# eeZeePot.net
KiCad netlist of a schematic drawn in EAGLE
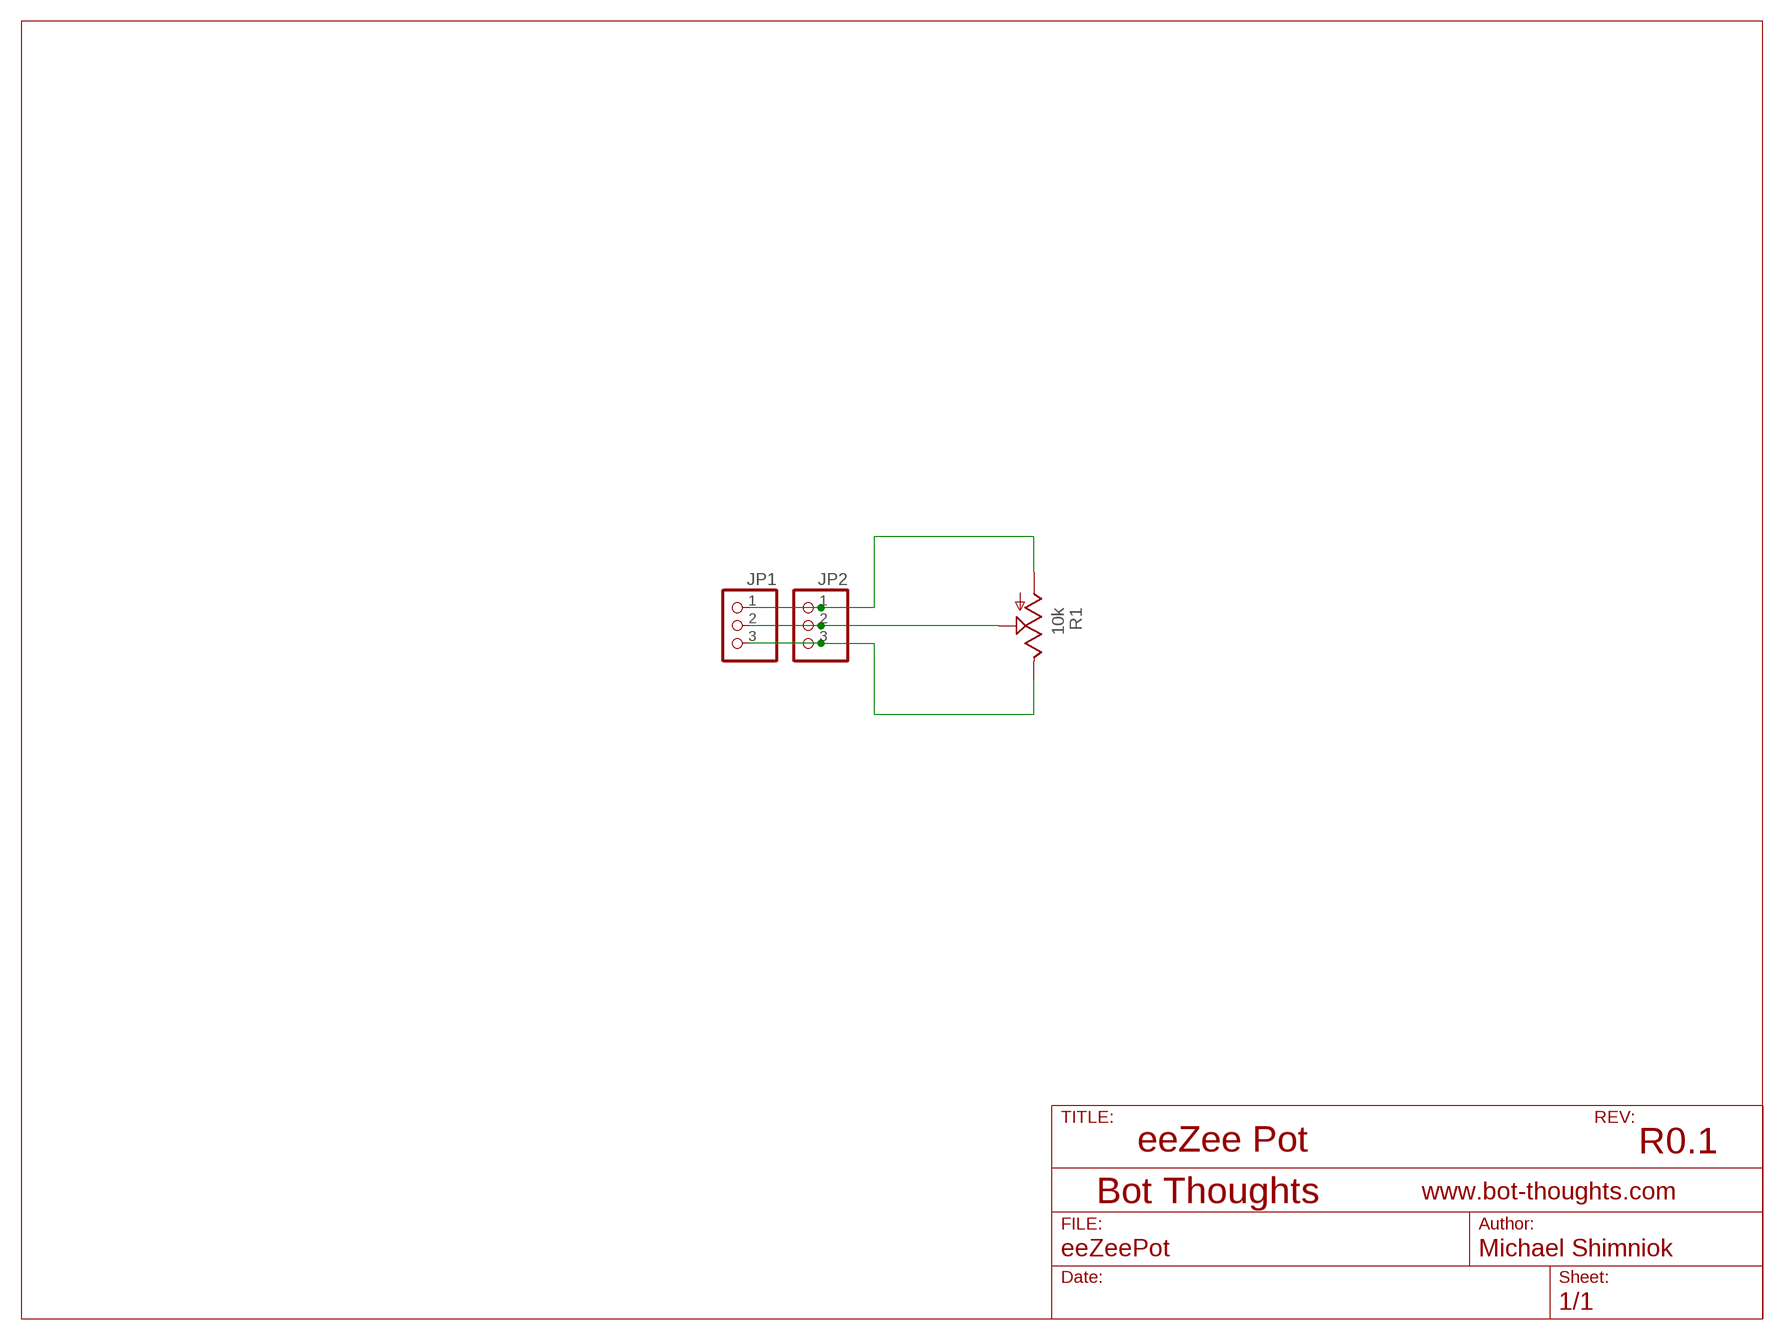
[diagram p0: schematic, sheet 1]

(export (version "E")
  (design (tool "Eeschema 10.0.6"))
  (components
    (comp (ref "JP1")
      (value "PINHD-1X03_2.54-S")
      (footprint "eagle-import:1X03-S")
      (libsource (lib "eagle-import") (part "PINHD-1X03_2.54-S"))
    )
    (comp (ref "JP2")
      (value "PINHD-1X03_2.54-S")
      (footprint "eagle-import:1X03-S")
      (libsource (lib "eagle-import") (part "PINHD-1X03_2.54-S"))
    )
    (comp (ref "R1")
      (value "10k")
      (footprint "eagle-import:CA6V")
      (libsource (lib "eagle-import") (part "TRIM_US-CA6V"))
    )
  )
  (nets
    (net (code "1") (name "Net-(JP1-Pad1)") (class "Default")
      (node (ref "JP1") (pin "1") (pinfunction "1_1") (pintype "passive"))
      (node (ref "JP2") (pin "1") (pinfunction "1_1") (pintype "passive"))
      (node (ref "R1") (pin "A") (pinfunction "A_A") (pintype "passive"))
    )
    (net (code "2") (name "Net-(JP1-Pad2)") (class "Default")
      (node (ref "JP1") (pin "2") (pinfunction "2_2") (pintype "passive"))
      (node (ref "JP2") (pin "2") (pinfunction "2_2") (pintype "passive"))
      (node (ref "R1") (pin "S") (pinfunction "S_S") (pintype "passive"))
    )
    (net (code "3") (name "Net-(JP1-Pad3)") (class "Default")
      (node (ref "JP1") (pin "3") (pinfunction "3_3") (pintype "passive"))
      (node (ref "JP2") (pin "3") (pinfunction "3_3") (pintype "passive"))
      (node (ref "R1") (pin "E") (pinfunction "E_E") (pintype "passive"))
    )
  )
)
